# MIU60_REVB.net
KiCad netlist of a schematic drawn in EAGLE
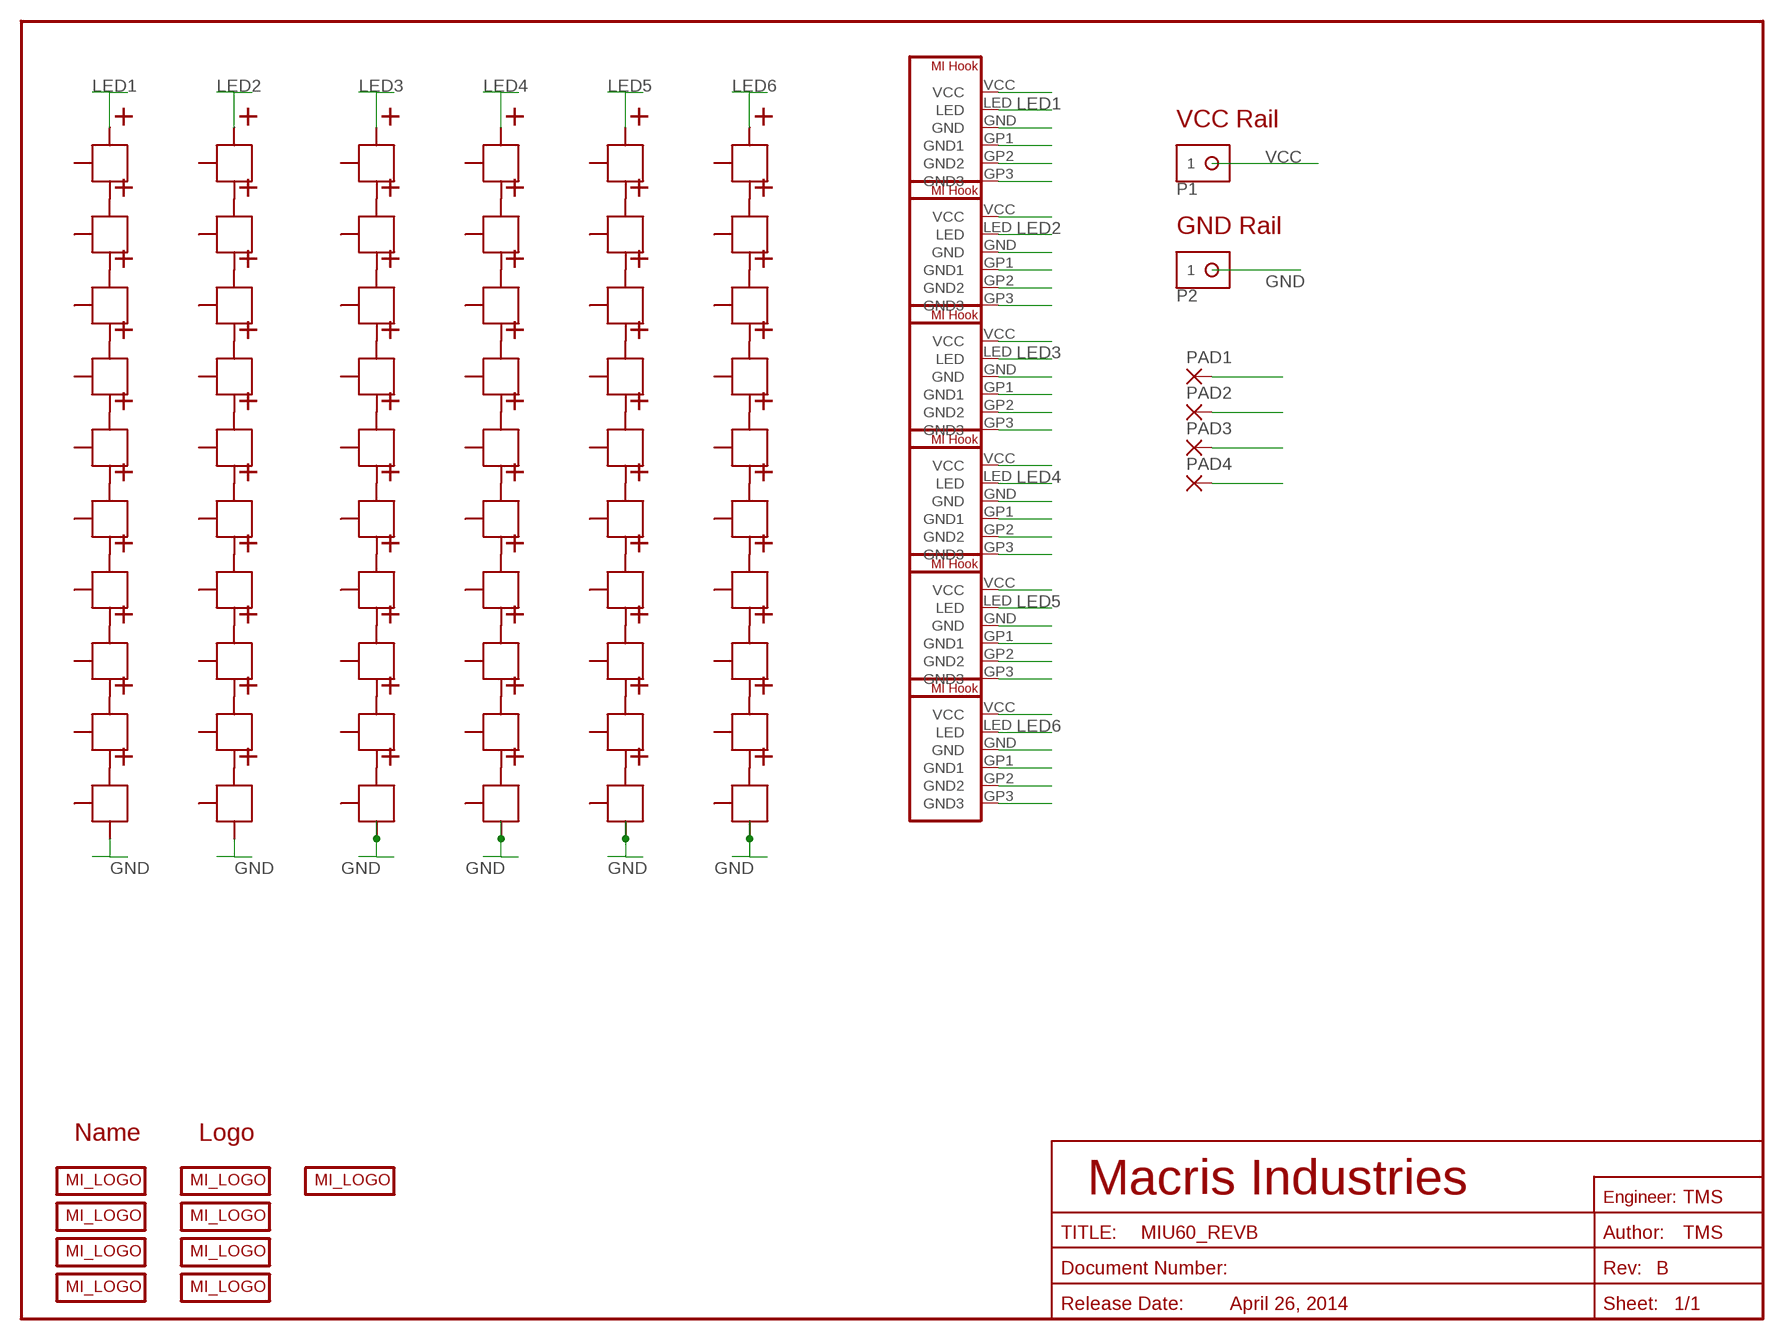
[diagram p0: schematic, sheet 1]

(export (version "E")
  (design (tool "Eeschema 10.0.6"))
  (components
    (comp (ref "P1")
      (value "PAD-10G")
      (footprint "eagle-import:PAD_10G")
      (libsource (lib "eagle-import") (part "PAD-10G"))
    )
    (comp (ref "P2")
      (value "PAD-10G")
      (footprint "eagle-import:PAD_10G")
      (libsource (lib "eagle-import") (part "PAD-10G"))
    )
    (comp (ref "PAD1")
      (value "SMD5")
      (footprint "eagle-import:SMD2,54-5,08")
      (libsource (lib "eagle-import") (part "SMD5"))
    )
    (comp (ref "PAD2")
      (value "SMD5")
      (footprint "eagle-import:SMD2,54-5,08")
      (libsource (lib "eagle-import") (part "SMD5"))
    )
    (comp (ref "PAD3")
      (value "SMD5")
      (footprint "eagle-import:SMD2,54-5,08")
      (libsource (lib "eagle-import") (part "SMD5"))
    )
    (comp (ref "PAD4")
      (value "SMD5")
      (footprint "eagle-import:SMD2,54-5,08")
      (libsource (lib "eagle-import") (part "SMD5"))
    )
    (comp (ref "U$1")
      (value "MI_LOGO-50MIL")
      (footprint "eagle-import:MI_LOGO_NAME_2")
      (libsource (lib "eagle-import") (part "MI_LOGO-NAME_TWO"))
    )
    (comp (ref "U$2")
      (value "MI_LOGO-2014_USA")
      (footprint "eagle-import:MACRIS_USA_LOGO")
      (libsource (lib "eagle-import") (part "MI_LOGO-2014_USA"))
    )
    (comp (ref "U$3")
      (value "MI_LOGO-50MIL")
      (footprint "eagle-import:MI_LOGO_NAME_2")
      (libsource (lib "eagle-import") (part "MI_LOGO-NAME_TWO"))
    )
    (comp (ref "U$4")
      (value "MI_LOGO-2014_USA")
      (footprint "eagle-import:MACRIS_USA_LOGO")
      (libsource (lib "eagle-import") (part "MI_LOGO-2014_USA"))
    )
    (comp (ref "U$5")
      (value "MI_LOGO-50MIL")
      (footprint "eagle-import:MI_LOGO_NAME_2")
      (libsource (lib "eagle-import") (part "MI_LOGO-NAME_TWO"))
    )
    (comp (ref "U$6")
      (value "MI_LOGO-50MIL")
      (footprint "eagle-import:MI_LOGO_NAME_2")
      (libsource (lib "eagle-import") (part "MI_LOGO-NAME_TWO"))
    )
    (comp (ref "U$7")
      (value "MI_LOGO-2014_USA")
      (footprint "eagle-import:MACRIS_USA_LOGO")
      (libsource (lib "eagle-import") (part "MI_LOGO-2014_USA"))
    )
    (comp (ref "U$8")
      (value "MI_LOGO-2014_USA")
      (footprint "eagle-import:MACRIS_USA_LOGO")
      (libsource (lib "eagle-import") (part "MI_LOGO-2014_USA"))
    )
    (comp (ref "U$9")
      (value "MI_DRIVER_HOOKUP")
      (footprint "eagle-import:MI_DRIVE_HOOKUP")
      (libsource (lib "eagle-import") (part "MI_DRIVER_HOOKUP"))
    )
    (comp (ref "U$10")
      (value "MI_DRIVER_HOOKUP")
      (footprint "eagle-import:MI_DRIVE_HOOKUP")
      (libsource (lib "eagle-import") (part "MI_DRIVER_HOOKUP"))
    )
    (comp (ref "U$11")
      (value "MI_DRIVER_HOOKUP")
      (footprint "eagle-import:MI_DRIVE_HOOKUP")
      (libsource (lib "eagle-import") (part "MI_DRIVER_HOOKUP"))
    )
    (comp (ref "U$12")
      (value "MI_DRIVER_HOOKUP")
      (footprint "eagle-import:MI_DRIVE_HOOKUP")
      (libsource (lib "eagle-import") (part "MI_DRIVER_HOOKUP"))
    )
    (comp (ref "U$13")
      (value "MI_DRIVER_HOOKUP")
      (footprint "eagle-import:MI_DRIVE_HOOKUP")
      (libsource (lib "eagle-import") (part "MI_DRIVER_HOOKUP"))
    )
    (comp (ref "U$14")
      (value "MI_DRIVER_HOOKUP")
      (footprint "eagle-import:MI_DRIVE_HOOKUP")
      (libsource (lib "eagle-import") (part "MI_DRIVER_HOOKUP"))
    )
    (comp (ref "U$15")
      (value "MI_LOGO")
      (footprint "eagle-import:MACRIS_MIU30")
      (libsource (lib "eagle-import") (part "MI_LOGO"))
    )
    (comp (ref "U$16")
      (value "CREE_XP")
      (footprint "eagle-import:XP")
      (libsource (lib "eagle-import") (part "CREE_XP"))
    )
    (comp (ref "U$17")
      (value "CREE_XP")
      (footprint "eagle-import:XP")
      (libsource (lib "eagle-import") (part "CREE_XP"))
    )
    (comp (ref "U$18")
      (value "CREE_XP")
      (footprint "eagle-import:XP")
      (libsource (lib "eagle-import") (part "CREE_XP"))
    )
    (comp (ref "U$19")
      (value "CREE_XP")
      (footprint "eagle-import:XP")
      (libsource (lib "eagle-import") (part "CREE_XP"))
    )
    (comp (ref "U$20")
      (value "CREE_XP")
      (footprint "eagle-import:XP")
      (libsource (lib "eagle-import") (part "CREE_XP"))
    )
    (comp (ref "U$21")
      (value "CREE_XP")
      (footprint "eagle-import:XP")
      (libsource (lib "eagle-import") (part "CREE_XP"))
    )
    (comp (ref "U$22")
      (value "CREE_XP")
      (footprint "eagle-import:XP")
      (libsource (lib "eagle-import") (part "CREE_XP"))
    )
    (comp (ref "U$23")
      (value "CREE_XP")
      (footprint "eagle-import:XP")
      (libsource (lib "eagle-import") (part "CREE_XP"))
    )
    (comp (ref "U$24")
      (value "CREE_XP")
      (footprint "eagle-import:XP")
      (libsource (lib "eagle-import") (part "CREE_XP"))
    )
    (comp (ref "U$25")
      (value "CREE_XP")
      (footprint "eagle-import:XP")
      (libsource (lib "eagle-import") (part "CREE_XP"))
    )
    (comp (ref "U$26")
      (value "CREE_XP")
      (footprint "eagle-import:XP")
      (libsource (lib "eagle-import") (part "CREE_XP"))
    )
    (comp (ref "U$27")
      (value "CREE_XP")
      (footprint "eagle-import:XP")
      (libsource (lib "eagle-import") (part "CREE_XP"))
    )
    (comp (ref "U$28")
      (value "CREE_XP")
      (footprint "eagle-import:XP")
      (libsource (lib "eagle-import") (part "CREE_XP"))
    )
    (comp (ref "U$29")
      (value "CREE_XP")
      (footprint "eagle-import:XP")
      (libsource (lib "eagle-import") (part "CREE_XP"))
    )
    (comp (ref "U$30")
      (value "CREE_XP")
      (footprint "eagle-import:XP")
      (libsource (lib "eagle-import") (part "CREE_XP"))
    )
    (comp (ref "U$31")
      (value "CREE_XP")
      (footprint "eagle-import:XP")
      (libsource (lib "eagle-import") (part "CREE_XP"))
    )
    (comp (ref "U$32")
      (value "CREE_XP")
      (footprint "eagle-import:XP")
      (libsource (lib "eagle-import") (part "CREE_XP"))
    )
    (comp (ref "U$33")
      (value "CREE_XP")
      (footprint "eagle-import:XP")
      (libsource (lib "eagle-import") (part "CREE_XP"))
    )
    (comp (ref "U$34")
      (value "CREE_XP")
      (footprint "eagle-import:XP")
      (libsource (lib "eagle-import") (part "CREE_XP"))
    )
    (comp (ref "U$35")
      (value "CREE_XP")
      (footprint "eagle-import:XP")
      (libsource (lib "eagle-import") (part "CREE_XP"))
    )
    (comp (ref "U$36")
      (value "CREE_XP")
      (footprint "eagle-import:XP")
      (libsource (lib "eagle-import") (part "CREE_XP"))
    )
    (comp (ref "U$37")
      (value "CREE_XP")
      (footprint "eagle-import:XP")
      (libsource (lib "eagle-import") (part "CREE_XP"))
    )
    (comp (ref "U$38")
      (value "CREE_XP")
      (footprint "eagle-import:XP")
      (libsource (lib "eagle-import") (part "CREE_XP"))
    )
    (comp (ref "U$39")
      (value "CREE_XP")
      (footprint "eagle-import:XP")
      (libsource (lib "eagle-import") (part "CREE_XP"))
    )
    (comp (ref "U$40")
      (value "CREE_XP")
      (footprint "eagle-import:XP")
      (libsource (lib "eagle-import") (part "CREE_XP"))
    )
    (comp (ref "U$41")
      (value "CREE_XP")
      (footprint "eagle-import:XP")
      (libsource (lib "eagle-import") (part "CREE_XP"))
    )
    (comp (ref "U$42")
      (value "CREE_XP")
      (footprint "eagle-import:XP")
      (libsource (lib "eagle-import") (part "CREE_XP"))
    )
    (comp (ref "U$43")
      (value "CREE_XP")
      (footprint "eagle-import:XP")
      (libsource (lib "eagle-import") (part "CREE_XP"))
    )
    (comp (ref "U$44")
      (value "CREE_XP")
      (footprint "eagle-import:XP")
      (libsource (lib "eagle-import") (part "CREE_XP"))
    )
    (comp (ref "U$45")
      (value "CREE_XP")
      (footprint "eagle-import:XP")
      (libsource (lib "eagle-import") (part "CREE_XP"))
    )
    (comp (ref "U$46")
      (value "CREE_XP")
      (footprint "eagle-import:XP")
      (libsource (lib "eagle-import") (part "CREE_XP"))
    )
    (comp (ref "U$47")
      (value "CREE_XP")
      (footprint "eagle-import:XP")
      (libsource (lib "eagle-import") (part "CREE_XP"))
    )
    (comp (ref "U$48")
      (value "CREE_XP")
      (footprint "eagle-import:XP")
      (libsource (lib "eagle-import") (part "CREE_XP"))
    )
    (comp (ref "U$49")
      (value "CREE_XP")
      (footprint "eagle-import:XP")
      (libsource (lib "eagle-import") (part "CREE_XP"))
    )
    (comp (ref "U$50")
      (value "CREE_XP")
      (footprint "eagle-import:XP")
      (libsource (lib "eagle-import") (part "CREE_XP"))
    )
    (comp (ref "U$51")
      (value "CREE_XP")
      (footprint "eagle-import:XP")
      (libsource (lib "eagle-import") (part "CREE_XP"))
    )
    (comp (ref "U$52")
      (value "CREE_XP")
      (footprint "eagle-import:XP")
      (libsource (lib "eagle-import") (part "CREE_XP"))
    )
    (comp (ref "U$53")
      (value "CREE_XP")
      (footprint "eagle-import:XP")
      (libsource (lib "eagle-import") (part "CREE_XP"))
    )
    (comp (ref "U$54")
      (value "CREE_XP")
      (footprint "eagle-import:XP")
      (libsource (lib "eagle-import") (part "CREE_XP"))
    )
    (comp (ref "U$55")
      (value "CREE_XP")
      (footprint "eagle-import:XP")
      (libsource (lib "eagle-import") (part "CREE_XP"))
    )
    (comp (ref "U$56")
      (value "CREE_XP")
      (footprint "eagle-import:XP")
      (libsource (lib "eagle-import") (part "CREE_XP"))
    )
    (comp (ref "U$57")
      (value "CREE_XP")
      (footprint "eagle-import:XP")
      (libsource (lib "eagle-import") (part "CREE_XP"))
    )
    (comp (ref "U$58")
      (value "CREE_XP")
      (footprint "eagle-import:XP")
      (libsource (lib "eagle-import") (part "CREE_XP"))
    )
    (comp (ref "U$59")
      (value "CREE_XP")
      (footprint "eagle-import:XP")
      (libsource (lib "eagle-import") (part "CREE_XP"))
    )
    (comp (ref "U$60")
      (value "CREE_XP")
      (footprint "eagle-import:XP")
      (libsource (lib "eagle-import") (part "CREE_XP"))
    )
    (comp (ref "U$61")
      (value "CREE_XP")
      (footprint "eagle-import:XP")
      (libsource (lib "eagle-import") (part "CREE_XP"))
    )
    (comp (ref "U$62")
      (value "CREE_XP")
      (footprint "eagle-import:XP")
      (libsource (lib "eagle-import") (part "CREE_XP"))
    )
    (comp (ref "U$63")
      (value "CREE_XP")
      (footprint "eagle-import:XP")
      (libsource (lib "eagle-import") (part "CREE_XP"))
    )
    (comp (ref "U$64")
      (value "CREE_XP")
      (footprint "eagle-import:XP")
      (libsource (lib "eagle-import") (part "CREE_XP"))
    )
    (comp (ref "U$65")
      (value "CREE_XP")
      (footprint "eagle-import:XP")
      (libsource (lib "eagle-import") (part "CREE_XP"))
    )
    (comp (ref "U$66")
      (value "CREE_XP")
      (footprint "eagle-import:XP")
      (libsource (lib "eagle-import") (part "CREE_XP"))
    )
    (comp (ref "U$67")
      (value "CREE_XP")
      (footprint "eagle-import:XP")
      (libsource (lib "eagle-import") (part "CREE_XP"))
    )
    (comp (ref "U$68")
      (value "CREE_XP")
      (footprint "eagle-import:XP")
      (libsource (lib "eagle-import") (part "CREE_XP"))
    )
    (comp (ref "U$69")
      (value "CREE_XP")
      (footprint "eagle-import:XP")
      (libsource (lib "eagle-import") (part "CREE_XP"))
    )
    (comp (ref "U$70")
      (value "CREE_XP")
      (footprint "eagle-import:XP")
      (libsource (lib "eagle-import") (part "CREE_XP"))
    )
    (comp (ref "U$71")
      (value "CREE_XP")
      (footprint "eagle-import:XP")
      (libsource (lib "eagle-import") (part "CREE_XP"))
    )
    (comp (ref "U$72")
      (value "CREE_XP")
      (footprint "eagle-import:XP")
      (libsource (lib "eagle-import") (part "CREE_XP"))
    )
    (comp (ref "U$73")
      (value "CREE_XP")
      (footprint "eagle-import:XP")
      (libsource (lib "eagle-import") (part "CREE_XP"))
    )
    (comp (ref "U$74")
      (value "CREE_XP")
      (footprint "eagle-import:XP")
      (libsource (lib "eagle-import") (part "CREE_XP"))
    )
    (comp (ref "U$75")
      (value "CREE_XP")
      (footprint "eagle-import:XP")
      (libsource (lib "eagle-import") (part "CREE_XP"))
    )
  )
  (nets
    (net (code "1") (name "/GND") (class "Default")
      (node (ref "P2") (pin "1") (pinfunction "1_1") (pintype "passive"))
      (node (ref "PAD3") (pin "1") (pinfunction "P_1") (pintype "passive"))
      (node (ref "PAD4") (pin "1") (pinfunction "P_1") (pintype "passive"))
      (node (ref "U$10") (pin "GND") (pinfunction "GND_GND") (pintype "bidirectional"))
      (node (ref "U$11") (pin "GND") (pinfunction "GND_GND") (pintype "bidirectional"))
      (node (ref "U$11") (pin "GP2") (pinfunction "GND2_GP2") (pintype "bidirectional"))
      (node (ref "U$12") (pin "GND") (pinfunction "GND_GND") (pintype "bidirectional"))
      (node (ref "U$12") (pin "GP2") (pinfunction "GND2_GP2") (pintype "bidirectional"))
      (node (ref "U$13") (pin "GND") (pinfunction "GND_GND") (pintype "bidirectional"))
      (node (ref "U$13") (pin "GP2") (pinfunction "GND2_GP2") (pintype "bidirectional"))
      (node (ref "U$14") (pin "GND") (pinfunction "GND_GND") (pintype "bidirectional"))
      (node (ref "U$14") (pin "GP2") (pinfunction "GND2_GP2") (pintype "bidirectional"))
      (node (ref "U$25") (pin "NEGATIVE") (pinfunction "NEGATIVE_NEGATIVE") (pintype "bidirectional"))
      (node (ref "U$25") (pin "NEGATIVE1") (pinfunction "NEGATIVE_NEGATIVE1") (pintype "bidirectional"))
      (node (ref "U$35") (pin "NEGATIVE") (pinfunction "NEGATIVE_NEGATIVE") (pintype "bidirectional"))
      (node (ref "U$35") (pin "NEGATIVE1") (pinfunction "NEGATIVE_NEGATIVE1") (pintype "bidirectional"))
      (node (ref "U$45") (pin "NEGATIVE") (pinfunction "NEGATIVE_NEGATIVE") (pintype "bidirectional"))
      (node (ref "U$45") (pin "NEGATIVE1") (pinfunction "NEGATIVE_NEGATIVE1") (pintype "bidirectional"))
      (node (ref "U$55") (pin "NEGATIVE") (pinfunction "NEGATIVE_NEGATIVE") (pintype "bidirectional"))
      (node (ref "U$55") (pin "NEGATIVE1") (pinfunction "NEGATIVE_NEGATIVE1") (pintype "bidirectional"))
      (node (ref "U$65") (pin "NEGATIVE") (pinfunction "NEGATIVE_NEGATIVE") (pintype "bidirectional"))
      (node (ref "U$65") (pin "NEGATIVE1") (pinfunction "NEGATIVE_NEGATIVE1") (pintype "bidirectional"))
      (node (ref "U$75") (pin "NEGATIVE") (pinfunction "NEGATIVE_NEGATIVE") (pintype "bidirectional"))
      (node (ref "U$75") (pin "NEGATIVE1") (pinfunction "NEGATIVE_NEGATIVE1") (pintype "bidirectional"))
      (node (ref "U$9") (pin "GND") (pinfunction "GND_GND") (pintype "bidirectional"))
      (node (ref "U$9") (pin "GP2") (pinfunction "GND2_GP2") (pintype "bidirectional"))
    )
    (net (code "2") (name "/LED1") (class "Default")
      (node (ref "U$16") (pin "POSITIVE") (pinfunction "POSITIVE_POSITIVE") (pintype "bidirectional"))
      (node (ref "U$16") (pin "POSITIVE1") (pinfunction "POSITIVE_POSITIVE1") (pintype "bidirectional"))
      (node (ref "U$9") (pin "LED") (pinfunction "LED_LED") (pintype "bidirectional"))
    )
    (net (code "3") (name "/LED2") (class "Default")
      (node (ref "U$10") (pin "LED") (pinfunction "LED_LED") (pintype "bidirectional"))
      (node (ref "U$26") (pin "POSITIVE") (pinfunction "POSITIVE_POSITIVE") (pintype "bidirectional"))
      (node (ref "U$26") (pin "POSITIVE1") (pinfunction "POSITIVE_POSITIVE1") (pintype "bidirectional"))
    )
    (net (code "4") (name "/LED3") (class "Default")
      (node (ref "U$11") (pin "LED") (pinfunction "LED_LED") (pintype "bidirectional"))
      (node (ref "U$36") (pin "POSITIVE") (pinfunction "POSITIVE_POSITIVE") (pintype "bidirectional"))
      (node (ref "U$36") (pin "POSITIVE1") (pinfunction "POSITIVE_POSITIVE1") (pintype "bidirectional"))
    )
    (net (code "5") (name "/LED4") (class "Default")
      (node (ref "U$12") (pin "LED") (pinfunction "LED_LED") (pintype "bidirectional"))
      (node (ref "U$46") (pin "POSITIVE") (pinfunction "POSITIVE_POSITIVE") (pintype "bidirectional"))
      (node (ref "U$46") (pin "POSITIVE1") (pinfunction "POSITIVE_POSITIVE1") (pintype "bidirectional"))
    )
    (net (code "6") (name "/LED5") (class "Default")
      (node (ref "U$13") (pin "LED") (pinfunction "LED_LED") (pintype "bidirectional"))
      (node (ref "U$56") (pin "POSITIVE") (pinfunction "POSITIVE_POSITIVE") (pintype "bidirectional"))
      (node (ref "U$56") (pin "POSITIVE1") (pinfunction "POSITIVE_POSITIVE1") (pintype "bidirectional"))
    )
    (net (code "7") (name "/LED6") (class "Default")
      (node (ref "U$14") (pin "LED") (pinfunction "LED_LED") (pintype "bidirectional"))
      (node (ref "U$66") (pin "POSITIVE") (pinfunction "POSITIVE_POSITIVE") (pintype "bidirectional"))
      (node (ref "U$66") (pin "POSITIVE1") (pinfunction "POSITIVE_POSITIVE1") (pintype "bidirectional"))
    )
    (net (code "8") (name "/VCC") (class "Default")
      (node (ref "P1") (pin "1") (pinfunction "1_1") (pintype "passive"))
      (node (ref "PAD1") (pin "1") (pinfunction "P_1") (pintype "passive"))
      (node (ref "PAD2") (pin "1") (pinfunction "P_1") (pintype "passive"))
      (node (ref "U$10") (pin "VCC") (pinfunction "VCC_VCC") (pintype "bidirectional"))
      (node (ref "U$11") (pin "VCC") (pinfunction "VCC_VCC") (pintype "bidirectional"))
      (node (ref "U$12") (pin "VCC") (pinfunction "VCC_VCC") (pintype "bidirectional"))
      (node (ref "U$13") (pin "VCC") (pinfunction "VCC_VCC") (pintype "bidirectional"))
      (node (ref "U$14") (pin "VCC") (pinfunction "VCC_VCC") (pintype "bidirectional"))
      (node (ref "U$9") (pin "VCC") (pinfunction "VCC_VCC") (pintype "bidirectional"))
    )
    (net (code "9") (name "Net-(U$16-NEGATIVE-PadNEGATIVE1)") (class "Default")
      (node (ref "U$16") (pin "NEGATIVE") (pinfunction "NEGATIVE_NEGATIVE") (pintype "bidirectional"))
      (node (ref "U$16") (pin "NEGATIVE1") (pinfunction "NEGATIVE_NEGATIVE1") (pintype "bidirectional"))
      (node (ref "U$17") (pin "POSITIVE") (pinfunction "POSITIVE_POSITIVE") (pintype "bidirectional"))
      (node (ref "U$17") (pin "POSITIVE1") (pinfunction "POSITIVE_POSITIVE1") (pintype "bidirectional"))
    )
    (net (code "10") (name "Net-(U$17-NEGATIVE-PadNEGATIVE1)") (class "Default")
      (node (ref "U$17") (pin "NEGATIVE") (pinfunction "NEGATIVE_NEGATIVE") (pintype "bidirectional"))
      (node (ref "U$17") (pin "NEGATIVE1") (pinfunction "NEGATIVE_NEGATIVE1") (pintype "bidirectional"))
      (node (ref "U$18") (pin "POSITIVE") (pinfunction "POSITIVE_POSITIVE") (pintype "bidirectional"))
      (node (ref "U$18") (pin "POSITIVE1") (pinfunction "POSITIVE_POSITIVE1") (pintype "bidirectional"))
    )
    (net (code "11") (name "Net-(U$18-NEGATIVE-PadNEGATIVE1)") (class "Default")
      (node (ref "U$18") (pin "NEGATIVE") (pinfunction "NEGATIVE_NEGATIVE") (pintype "bidirectional"))
      (node (ref "U$18") (pin "NEGATIVE1") (pinfunction "NEGATIVE_NEGATIVE1") (pintype "bidirectional"))
      (node (ref "U$19") (pin "POSITIVE") (pinfunction "POSITIVE_POSITIVE") (pintype "bidirectional"))
      (node (ref "U$19") (pin "POSITIVE1") (pinfunction "POSITIVE_POSITIVE1") (pintype "bidirectional"))
    )
    (net (code "12") (name "Net-(U$19-NEGATIVE-PadNEGATIVE1)") (class "Default")
      (node (ref "U$19") (pin "NEGATIVE") (pinfunction "NEGATIVE_NEGATIVE") (pintype "bidirectional"))
      (node (ref "U$19") (pin "NEGATIVE1") (pinfunction "NEGATIVE_NEGATIVE1") (pintype "bidirectional"))
      (node (ref "U$20") (pin "POSITIVE") (pinfunction "POSITIVE_POSITIVE") (pintype "bidirectional"))
      (node (ref "U$20") (pin "POSITIVE1") (pinfunction "POSITIVE_POSITIVE1") (pintype "bidirectional"))
    )
    (net (code "13") (name "Net-(U$20-NEGATIVE-PadNEGATIVE1)") (class "Default")
      (node (ref "U$20") (pin "NEGATIVE") (pinfunction "NEGATIVE_NEGATIVE") (pintype "bidirectional"))
      (node (ref "U$20") (pin "NEGATIVE1") (pinfunction "NEGATIVE_NEGATIVE1") (pintype "bidirectional"))
      (node (ref "U$21") (pin "POSITIVE") (pinfunction "POSITIVE_POSITIVE") (pintype "bidirectional"))
      (node (ref "U$21") (pin "POSITIVE1") (pinfunction "POSITIVE_POSITIVE1") (pintype "bidirectional"))
    )
    (net (code "14") (name "Net-(U$21-NEGATIVE-PadNEGATIVE1)") (class "Default")
      (node (ref "U$21") (pin "NEGATIVE") (pinfunction "NEGATIVE_NEGATIVE") (pintype "bidirectional"))
      (node (ref "U$21") (pin "NEGATIVE1") (pinfunction "NEGATIVE_NEGATIVE1") (pintype "bidirectional"))
      (node (ref "U$22") (pin "POSITIVE") (pinfunction "POSITIVE_POSITIVE") (pintype "bidirectional"))
      (node (ref "U$22") (pin "POSITIVE1") (pinfunction "POSITIVE_POSITIVE1") (pintype "bidirectional"))
    )
    (net (code "15") (name "Net-(U$22-NEGATIVE-PadNEGATIVE1)") (class "Default")
      (node (ref "U$22") (pin "NEGATIVE") (pinfunction "NEGATIVE_NEGATIVE") (pintype "bidirectional"))
      (node (ref "U$22") (pin "NEGATIVE1") (pinfunction "NEGATIVE_NEGATIVE1") (pintype "bidirectional"))
      (node (ref "U$23") (pin "POSITIVE") (pinfunction "POSITIVE_POSITIVE") (pintype "bidirectional"))
      (node (ref "U$23") (pin "POSITIVE1") (pinfunction "POSITIVE_POSITIVE1") (pintype "bidirectional"))
    )
    (net (code "16") (name "Net-(U$23-NEGATIVE-PadNEGATIVE1)") (class "Default")
      (node (ref "U$23") (pin "NEGATIVE") (pinfunction "NEGATIVE_NEGATIVE") (pintype "bidirectional"))
      (node (ref "U$23") (pin "NEGATIVE1") (pinfunction "NEGATIVE_NEGATIVE1") (pintype "bidirectional"))
      (node (ref "U$24") (pin "POSITIVE") (pinfunction "POSITIVE_POSITIVE") (pintype "bidirectional"))
      (node (ref "U$24") (pin "POSITIVE1") (pinfunction "POSITIVE_POSITIVE1") (pintype "bidirectional"))
    )
    (net (code "17") (name "Net-(U$24-NEGATIVE-PadNEGATIVE1)") (class "Default")
      (node (ref "U$24") (pin "NEGATIVE") (pinfunction "NEGATIVE_NEGATIVE") (pintype "bidirectional"))
      (node (ref "U$24") (pin "NEGATIVE1") (pinfunction "NEGATIVE_NEGATIVE1") (pintype "bidirectional"))
      (node (ref "U$25") (pin "POSITIVE") (pinfunction "POSITIVE_POSITIVE") (pintype "bidirectional"))
      (node (ref "U$25") (pin "POSITIVE1") (pinfunction "POSITIVE_POSITIVE1") (pintype "bidirectional"))
    )
    (net (code "18") (name "Net-(U$26-NEGATIVE-PadNEGATIVE1)") (class "Default")
      (node (ref "U$26") (pin "NEGATIVE") (pinfunction "NEGATIVE_NEGATIVE") (pintype "bidirectional"))
      (node (ref "U$26") (pin "NEGATIVE1") (pinfunction "NEGATIVE_NEGATIVE1") (pintype "bidirectional"))
      (node (ref "U$27") (pin "POSITIVE") (pinfunction "POSITIVE_POSITIVE") (pintype "bidirectional"))
      (node (ref "U$27") (pin "POSITIVE1") (pinfunction "POSITIVE_POSITIVE1") (pintype "bidirectional"))
    )
    (net (code "19") (name "Net-(U$27-NEGATIVE-PadNEGATIVE1)") (class "Default")
      (node (ref "U$27") (pin "NEGATIVE") (pinfunction "NEGATIVE_NEGATIVE") (pintype "bidirectional"))
      (node (ref "U$27") (pin "NEGATIVE1") (pinfunction "NEGATIVE_NEGATIVE1") (pintype "bidirectional"))
      (node (ref "U$28") (pin "POSITIVE") (pinfunction "POSITIVE_POSITIVE") (pintype "bidirectional"))
      (node (ref "U$28") (pin "POSITIVE1") (pinfunction "POSITIVE_POSITIVE1") (pintype "bidirectional"))
    )
    (net (code "20") (name "Net-(U$28-NEGATIVE-PadNEGATIVE1)") (class "Default")
      (node (ref "U$28") (pin "NEGATIVE") (pinfunction "NEGATIVE_NEGATIVE") (pintype "bidirectional"))
      (node (ref "U$28") (pin "NEGATIVE1") (pinfunction "NEGATIVE_NEGATIVE1") (pintype "bidirectional"))
      (node (ref "U$29") (pin "POSITIVE") (pinfunction "POSITIVE_POSITIVE") (pintype "bidirectional"))
      (node (ref "U$29") (pin "POSITIVE1") (pinfunction "POSITIVE_POSITIVE1") (pintype "bidirectional"))
    )
    (net (code "21") (name "Net-(U$29-NEGATIVE-PadNEGATIVE1)") (class "Default")
      (node (ref "U$29") (pin "NEGATIVE") (pinfunction "NEGATIVE_NEGATIVE") (pintype "bidirectional"))
      (node (ref "U$29") (pin "NEGATIVE1") (pinfunction "NEGATIVE_NEGATIVE1") (pintype "bidirectional"))
      (node (ref "U$30") (pin "POSITIVE") (pinfunction "POSITIVE_POSITIVE") (pintype "bidirectional"))
      (node (ref "U$30") (pin "POSITIVE1") (pinfunction "POSITIVE_POSITIVE1") (pintype "bidirectional"))
    )
    (net (code "22") (name "Net-(U$30-NEGATIVE-PadNEGATIVE1)") (class "Default")
      (node (ref "U$30") (pin "NEGATIVE") (pinfunction "NEGATIVE_NEGATIVE") (pintype "bidirectional"))
      (node (ref "U$30") (pin "NEGATIVE1") (pinfunction "NEGATIVE_NEGATIVE1") (pintype "bidirectional"))
      (node (ref "U$31") (pin "POSITIVE") (pinfunction "POSITIVE_POSITIVE") (pintype "bidirectional"))
      (node (ref "U$31") (pin "POSITIVE1") (pinfunction "POSITIVE_POSITIVE1") (pintype "bidirectional"))
    )
    (net (code "23") (name "Net-(U$31-NEGATIVE-PadNEGATIVE1)") (class "Default")
      (node (ref "U$31") (pin "NEGATIVE") (pinfunction "NEGATIVE_NEGATIVE") (pintype "bidirectional"))
      (node (ref "U$31") (pin "NEGATIVE1") (pinfunction "NEGATIVE_NEGATIVE1") (pintype "bidirectional"))
      (node (ref "U$32") (pin "POSITIVE") (pinfunction "POSITIVE_POSITIVE") (pintype "bidirectional"))
      (node (ref "U$32") (pin "POSITIVE1") (pinfunction "POSITIVE_POSITIVE1") (pintype "bidirectional"))
    )
    (net (code "24") (name "Net-(U$32-NEGATIVE-PadNEGATIVE1)") (class "Default")
      (node (ref "U$32") (pin "NEGATIVE") (pinfunction "NEGATIVE_NEGATIVE") (pintype "bidirectional"))
      (node (ref "U$32") (pin "NEGATIVE1") (pinfunction "NEGATIVE_NEGATIVE1") (pintype "bidirectional"))
      (node (ref "U$33") (pin "POSITIVE") (pinfunction "POSITIVE_POSITIVE") (pintype "bidirectional"))
      (node (ref "U$33") (pin "POSITIVE1") (pinfunction "POSITIVE_POSITIVE1") (pintype "bidirectional"))
    )
    (net (code "25") (name "Net-(U$33-NEGATIVE-PadNEGATIVE1)") (class "Default")
      (node (ref "U$33") (pin "NEGATIVE") (pinfunction "NEGATIVE_NEGATIVE") (pintype "bidirectional"))
      (node (ref "U$33") (pin "NEGATIVE1") (pinfunction "NEGATIVE_NEGATIVE1") (pintype "bidirectional"))
      (node (ref "U$34") (pin "POSITIVE") (pinfunction "POSITIVE_POSITIVE") (pintype "bidirectional"))
      (node (ref "U$34") (pin "POSITIVE1") (pinfunction "POSITIVE_POSITIVE1") (pintype "bidirectional"))
    )
    (net (code "26") (name "Net-(U$34-NEGATIVE-PadNEGATIVE1)") (class "Default")
      (node (ref "U$34") (pin "NEGATIVE") (pinfunction "NEGATIVE_NEGATIVE") (pintype "bidirectional"))
      (node (ref "U$34") (pin "NEGATIVE1") (pinfunction "NEGATIVE_NEGATIVE1") (pintype "bidirectional"))
      (node (ref "U$35") (pin "POSITIVE") (pinfunction "POSITIVE_POSITIVE") (pintype "bidirectional"))
      (node (ref "U$35") (pin "POSITIVE1") (pinfunction "POSITIVE_POSITIVE1") (pintype "bidirectional"))
    )
    (net (code "27") (name "Net-(U$36-NEGATIVE-PadNEGATIVE1)") (class "Default")
      (node (ref "U$36") (pin "NEGATIVE") (pinfunction "NEGATIVE_NEGATIVE") (pintype "bidirectional"))
      (node (ref "U$36") (pin "NEGATIVE1") (pinfunction "NEGATIVE_NEGATIVE1") (pintype "bidirectional"))
      (node (ref "U$37") (pin "POSITIVE") (pinfunction "POSITIVE_POSITIVE") (pintype "bidirectional"))
      (node (ref "U$37") (pin "POSITIVE1") (pinfunction "POSITIVE_POSITIVE1") (pintype "bidirectional"))
    )
    (net (code "28") (name "Net-(U$37-NEGATIVE-PadNEGATIVE1)") (class "Default")
      (node (ref "U$37") (pin "NEGATIVE") (pinfunction "NEGATIVE_NEGATIVE") (pintype "bidirectional"))
      (node (ref "U$37") (pin "NEGATIVE1") (pinfunction "NEGATIVE_NEGATIVE1") (pintype "bidirectional"))
      (node (ref "U$38") (pin "POSITIVE") (pinfunction "POSITIVE_POSITIVE") (pintype "bidirectional"))
      (node (ref "U$38") (pin "POSITIVE1") (pinfunction "POSITIVE_POSITIVE1") (pintype "bidirectional"))
    )
    (net (code "29") (name "Net-(U$38-NEGATIVE-PadNEGATIVE1)") (class "Default")
      (node (ref "U$38") (pin "NEGATIVE") (pinfunction "NEGATIVE_NEGATIVE") (pintype "bidirectional"))
      (node (ref "U$38") (pin "NEGATIVE1") (pinfunction "NEGATIVE_NEGATIVE1") (pintype "bidirectional"))
      (node (ref "U$39") (pin "POSITIVE") (pinfunction "POSITIVE_POSITIVE") (pintype "bidirectional"))
      (node (ref "U$39") (pin "POSITIVE1") (pinfunction "POSITIVE_POSITIVE1") (pintype "bidirectional"))
    )
    (net (code "30") (name "Net-(U$39-NEGATIVE-PadNEGATIVE1)") (class "Default")
      (node (ref "U$39") (pin "NEGATIVE") (pinfunction "NEGATIVE_NEGATIVE") (pintype "bidirectional"))
      (node (ref "U$39") (pin "NEGATIVE1") (pinfunction "NEGATIVE_NEGATIVE1") (pintype "bidirectional"))
      (node (ref "U$40") (pin "POSITIVE") (pinfunction "POSITIVE_POSITIVE") (pintype "bidirectional"))
      (node (ref "U$40") (pin "POSITIVE1") (pinfunction "POSITIVE_POSITIVE1") (pintype "bidirectional"))
    )
    (net (code "31") (name "Net-(U$40-NEGATIVE-PadNEGATIVE1)") (class "Default")
      (node (ref "U$40") (pin "NEGATIVE") (pinfunction "NEGATIVE_NEGATIVE") (pintype "bidirectional"))
      (node (ref "U$40") (pin "NEGATIVE1") (pinfunction "NEGATIVE_NEGATIVE1") (pintype "bidirectional"))
      (node (ref "U$41") (pin "POSITIVE") (pinfunction "POSITIVE_POSITIVE") (pintype "bidirectional"))
      (node (ref "U$41") (pin "POSITIVE1") (pinfunction "POSITIVE_POSITIVE1") (pintype "bidirectional"))
    )
    (net (code "32") (name "Net-(U$41-NEGATIVE-PadNEGATIVE1)") (class "Default")
      (node (ref "U$41") (pin "NEGATIVE") (pinfunction "NEGATIVE_NEGATIVE") (pintype "bidirectional"))
      (node (ref "U$41") (pin "NEGATIVE1") (pinfunction "NEGATIVE_NEGATIVE1") (pintype "bidirectional"))
      (node (ref "U$42") (pin "POSITIVE") (pinfunction "POSITIVE_POSITIVE") (pintype "bidirectional"))
      (node (ref "U$42") (pin "POSITIVE1") (pinfunction "POSITIVE_POSITIVE1") (pintype "bidirectional"))
    )
    (net (code "33") (name "Net-(U$42-NEGATIVE-PadNEGATIVE1)") (class "Default")
      (node (ref "U$42") (pin "NEGATIVE") (pinfunction "NEGATIVE_NEGATIVE") (pintype "bidirectional"))
      (node (ref "U$42") (pin "NEGATIVE1") (pinfunction "NEGATIVE_NEGATIVE1") (pintype "bidirectional"))
      (node (ref "U$43") (pin "POSITIVE") (pinfunction "POSITIVE_POSITIVE") (pintype "bidirectional"))
      (node (ref "U$43") (pin "POSITIVE1") (pinfunction "POSITIVE_POSITIVE1") (pintype "bidirectional"))
    )
    (net (code "34") (name "Net-(U$43-NEGATIVE-PadNEGATIVE1)") (class "Default")
      (node (ref "U$43") (pin "NEGATIVE") (pinfunction "NEGATIVE_NEGATIVE") (pintype "bidirectional"))
      (node (ref "U$43") (pin "NEGATIVE1") (pinfunction "NEGATIVE_NEGATIVE1") (pintype "bidirectional"))
      (node (ref "U$44") (pin "POSITIVE") (pinfunction "POSITIVE_POSITIVE") (pintype "bidirectional"))
      (node (ref "U$44") (pin "POSITIVE1") (pinfunction "POSITIVE_POSITIVE1") (pintype "bidirectional"))
    )
    (net (code "35") (name "Net-(U$44-NEGATIVE-PadNEGATIVE1)") (class "Default")
      (node (ref "U$44") (pin "NEGATIVE") (pinfunction "NEGATIVE_NEGATIVE") (pintype "bidirectional"))
      (node (ref "U$44") (pin "NEGATIVE1") (pinfunction "NEGATIVE_NEGATIVE1") (pintype "bidirectional"))
      (node (ref "U$45") (pin "POSITIVE") (pinfunction "POSITIVE_POSITIVE") (pintype "bidirectional"))
      (node (ref "U$45") (pin "POSITIVE1") (pinfunction "POSITIVE_POSITIVE1") (pintype "bidirectional"))
    )
    (net (code "36") (name "Net-(U$46-NEGATIVE-PadNEGATIVE1)") (class "Default")
      (node (ref "U$46") (pin "NEGATIVE") (pinfunction "NEGATIVE_NEGATIVE") (pintype "bidirectional"))
      (node (ref "U$46") (pin "NEGATIVE1") (pinfunction "NEGATIVE_NEGATIVE1") (pintype "bidirectional"))
      (node (ref "U$47") (pin "POSITIVE") (pinfunction "POSITIVE_POSITIVE") (pintype "bidirectional"))
      (node (ref "U$47") (pin "POSITIVE1") (pinfunction "POSITIVE_POSITIVE1") (pintype "bidirectional"))
    )
    (net (code "37") (name "Net-(U$47-NEGATIVE-PadNEGATIVE1)") (class "Default")
      (node (ref "U$47") (pin "NEGATIVE") (pinfunction "NEGATIVE_NEGATIVE") (pintype "bidirectional"))
      (node (ref "U$47") (pin "NEGATIVE1") (pinfunction "NEGATIVE_NEGATIVE1") (pintype "bidirectional"))
      (node (ref "U$48") (pin "POSITIVE") (pinfunction "POSITIVE_POSITIVE") (pintype "bidirectional"))
      (node (ref "U$48") (pin "POSITIVE1") (pinfunction "POSITIVE_POSITIVE1") (pintype "bidirectional"))
    )
    (net (code "38") (name "Net-(U$48-NEGATIVE-PadNEGATIVE1)") (class "Default")
      (node (ref "U$48") (pin "NEGATIVE") (pinfunction "NEGATIVE_NEGATIVE") (pintype "bidirectional"))
      (node (ref "U$48") (pin "NEGATIVE1") (pinfunction "NEGATIVE_NEGATIVE1") (pintype "bidirectional"))
      (node (ref "U$49") (pin "POSITIVE") (pinfunction "POSITIVE_POSITIVE") (pintype "bidirectional"))
      (node (ref "U$49") (pin "POSITIVE1") (pinfunction "POSITIVE_POSITIVE1") (pintype "bidirectional"))
    )
    (net (code "39") (name "Net-(U$49-NEGATIVE-PadNEGATIVE1)") (class "Default")
      (node (ref "U$49") (pin "NEGATIVE") (pinfunction "NEGATIVE_NEGATIVE") (pintype "bidirectional"))
      (node (ref "U$49") (pin "NEGATIVE1") (pinfunction "NEGATIVE_NEGATIVE1") (pintype "bidirectional"))
      (node (ref "U$50") (pin "POSITIVE") (pinfunction "POSITIVE_POSITIVE") (pintype "bidirectional"))
      (node (ref "U$50") (pin "POSITIVE1") (pinfunction "POSITIVE_POSITIVE1") (pintype "bidirectional"))
    )
    (net (code "40") (name "Net-(U$50-NEGATIVE-PadNEGATIVE1)") (class "Default")
      (node (ref "U$50") (pin "NEGATIVE") (pinfunction "NEGATIVE_NEGATIVE") (pintype "bidirectional"))
      (node (ref "U$50") (pin "NEGATIVE1") (pinfunction "NEGATIVE_NEGATIVE1") (pintype "bidirectional"))
      (node (ref "U$51") (pin "POSITIVE") (pinfunction "POSITIVE_POSITIVE") (pintype "bidirectional"))
      (node (ref "U$51") (pin "POSITIVE1") (pinfunction "POSITIVE_POSITIVE1") (pintype "bidirectional"))
    )
    (net (code "41") (name "Net-(U$51-NEGATIVE-PadNEGATIVE1)") (class "Default")
      (node (ref "U$51") (pin "NEGATIVE") (pinfunction "NEGATIVE_NEGATIVE") (pintype "bidirectional"))
      (node (ref "U$51") (pin "NEGATIVE1") (pinfunction "NEGATIVE_NEGATIVE1") (pintype "bidirectional"))
      (node (ref "U$52") (pin "POSITIVE") (pinfunction "POSITIVE_POSITIVE") (pintype "bidirectional"))
      (node (ref "U$52") (pin "POSITIVE1") (pinfunction "POSITIVE_POSITIVE1") (pintype "bidirectional"))
    )
    (net (code "42") (name "Net-(U$52-NEGATIVE-PadNEGATIVE1)") (class "Default")
      (node (ref "U$52") (pin "NEGATIVE") (pinfunction "NEGATIVE_NEGATIVE") (pintype "bidirectional"))
      (node (ref "U$52") (pin "NEGATIVE1") (pinfunction "NEGATIVE_NEGATIVE1") (pintype "bidirectional"))
      (node (ref "U$53") (pin "POSITIVE") (pinfunction "POSITIVE_POSITIVE") (pintype "bidirectional"))
      (node (ref "U$53") (pin "POSITIVE1") (pinfunction "POSITIVE_POSITIVE1") (pintype "bidirectional"))
    )
    (net (code "43") (name "Net-(U$53-NEGATIVE-PadNEGATIVE1)") (class "Default")
      (node (ref "U$53") (pin "NEGATIVE") (pinfunction "NEGATIVE_NEGATIVE") (pintype "bidirectional"))
      (node (ref "U$53") (pin "NEGATIVE1") (pinfunction "NEGATIVE_NEGATIVE1") (pintype "bidirectional"))
      (node (ref "U$54") (pin "POSITIVE") (pinfunction "POSITIVE_POSITIVE") (pintype "bidirectional"))
      (node (ref "U$54") (pin "POSITIVE1") (pinfunction "POSITIVE_POSITIVE1") (pintype "bidirectional"))
    )
    (net (code "44") (name "Net-(U$54-NEGATIVE-PadNEGATIVE1)") (class "Default")
      (node (ref "U$54") (pin "NEGATIVE") (pinfunction "NEGATIVE_NEGATIVE") (pintype "bidirectional"))
      (node (ref "U$54") (pin "NEGATIVE1") (pinfunction "NEGATIVE_NEGATIVE1") (pintype "bidirectional"))
      (node (ref "U$55") (pin "POSITIVE") (pinfunction "POSITIVE_POSITIVE") (pintype "bidirectional"))
      (node (ref "U$55") (pin "POSITIVE1") (pinfunction "POSITIVE_POSITIVE1") (pintype "bidirectional"))
    )
    (net (code "45") (name "Net-(U$56-NEGATIVE-PadNEGATIVE1)") (class "Default")
      (node (ref "U$56") (pin "NEGATIVE") (pinfunction "NEGATIVE_NEGATIVE") (pintype "bidirectional"))
      (node (ref "U$56") (pin "NEGATIVE1") (pinfunction "NEGATIVE_NEGATIVE1") (pintype "bidirectional"))
      (node (ref "U$57") (pin "POSITIVE") (pinfunction "POSITIVE_POSITIVE") (pintype "bidirectional"))
      (node (ref "U$57") (pin "POSITIVE1") (pinfunction "POSITIVE_POSITIVE1") (pintype "bidirectional"))
    )
    (net (code "46") (name "Net-(U$57-NEGATIVE-PadNEGATIVE1)") (class "Default")
      (node (ref "U$57") (pin "NEGATIVE") (pinfunction "NEGATIVE_NEGATIVE") (pintype "bidirectional"))
      (node (ref "U$57") (pin "NEGATIVE1") (pinfunction "NEGATIVE_NEGATIVE1") (pintype "bidirectional"))
      (node (ref "U$58") (pin "POSITIVE") (pinfunction "POSITIVE_POSITIVE") (pintype "bidirectional"))
      (node (ref "U$58") (pin "POSITIVE1") (pinfunction "POSITIVE_POSITIVE1") (pintype "bidirectional"))
    )
    (net (code "47") (name "Net-(U$58-NEGATIVE-PadNEGATIVE1)") (class "Default")
      (node (ref "U$58") (pin "NEGATIVE") (pinfunction "NEGATIVE_NEGATIVE") (pintype "bidirectional"))
      (node (ref "U$58") (pin "NEGATIVE1") (pinfunction "NEGATIVE_NEGATIVE1") (pintype "bidirectional"))
      (node (ref "U$59") (pin "POSITIVE") (pinfunction "POSITIVE_POSITIVE") (pintype "bidirectional"))
      (node (ref "U$59") (pin "POSITIVE1") (pinfunction "POSITIVE_POSITIVE1") (pintype "bidirectional"))
    )
    (net (code "48") (name "Net-(U$59-NEGATIVE-PadNEGATIVE1)") (class "Default")
      (node (ref "U$59") (pin "NEGATIVE") (pinfunction "NEGATIVE_NEGATIVE") (pintype "bidirectional"))
      (node (ref "U$59") (pin "NEGATIVE1") (pinfunction "NEGATIVE_NEGATIVE1") (pintype "bidirectional"))
      (node (ref "U$60") (pin "POSITIVE") (pinfunction "POSITIVE_POSITIVE") (pintype "bidirectional"))
      (node (ref "U$60") (pin "POSITIVE1") (pinfunction "POSITIVE_POSITIVE1") (pintype "bidirectional"))
    )
    (net (code "49") (name "Net-(U$60-NEGATIVE-PadNEGATIVE1)") (class "Default")
      (node (ref "U$60") (pin "NEGATIVE") (pinfunction "NEGATIVE_NEGATIVE") (pintype "bidirectional"))
      (node (ref "U$60") (pin "NEGATIVE1") (pinfunction "NEGATIVE_NEGATIVE1") (pintype "bidirectional"))
      (node (ref "U$61") (pin "POSITIVE") (pinfunction "POSITIVE_POSITIVE") (pintype "bidirectional"))
      (node (ref "U$61") (pin "POSITIVE1") (pinfunction "POSITIVE_POSITIVE1") (pintype "bidirectional"))
    )
    (net (code "50") (name "Net-(U$61-NEGATIVE-PadNEGATIVE1)") (class "Default")
      (node (ref "U$61") (pin "NEGATIVE") (pinfunction "NEGATIVE_NEGATIVE") (pintype "bidirectional"))
      (node (ref "U$61") (pin "NEGATIVE1") (pinfunction "NEGATIVE_NEGATIVE1") (pintype "bidirectional"))
      (node (ref "U$62") (pin "POSITIVE") (pinfunction "POSITIVE_POSITIVE") (pintype "bidirectional"))
      (node (ref "U$62") (pin "POSITIVE1") (pinfunction "POSITIVE_POSITIVE1") (pintype "bidirectional"))
    )
    (net (code "51") (name "Net-(U$62-NEGATIVE-PadNEGATIVE1)") (class "Default")
      (node (ref "U$62") (pin "NEGATIVE") (pinfunction "NEGATIVE_NEGATIVE") (pintype "bidirectional"))
      (node (ref "U$62") (pin "NEGATIVE1") (pinfunction "NEGATIVE_NEGATIVE1") (pintype "bidirectional"))
      (node (ref "U$63") (pin "POSITIVE") (pinfunction "POSITIVE_POSITIVE") (pintype "bidirectional"))
      (node (ref "U$63") (pin "POSITIVE1") (pinfunction "POSITIVE_POSITIVE1") (pintype "bidirectional"))
    )
    (net (code "52") (name "Net-(U$63-NEGATIVE-PadNEGATIVE1)") (class "Default")
      (node (ref "U$63") (pin "NEGATIVE") (pinfunction "NEGATIVE_NEGATIVE") (pintype "bidirectional"))
      (node (ref "U$63") (pin "NEGATIVE1") (pinfunction "NEGATIVE_NEGATIVE1") (pintype "bidirectional"))
      (node (ref "U$64") (pin "POSITIVE") (pinfunction "POSITIVE_POSITIVE") (pintype "bidirectional"))
      (node (ref "U$64") (pin "POSITIVE1") (pinfunction "POSITIVE_POSITIVE1") (pintype "bidirectional"))
    )
    (net (code "53") (name "Net-(U$64-NEGATIVE-PadNEGATIVE1)") (class "Default")
      (node (ref "U$64") (pin "NEGATIVE") (pinfunction "NEGATIVE_NEGATIVE") (pintype "bidirectional"))
      (node (ref "U$64") (pin "NEGATIVE1") (pinfunction "NEGATIVE_NEGATIVE1") (pintype "bidirectional"))
      (node (ref "U$65") (pin "POSITIVE") (pinfunction "POSITIVE_POSITIVE") (pintype "bidirectional"))
      (node (ref "U$65") (pin "POSITIVE1") (pinfunction "POSITIVE_POSITIVE1") (pintype "bidirectional"))
    )
    (net (code "54") (name "Net-(U$66-NEGATIVE-PadNEGATIVE1)") (class "Default")
      (node (ref "U$66") (pin "NEGATIVE") (pinfunction "NEGATIVE_NEGATIVE") (pintype "bidirectional"))
      (node (ref "U$66") (pin "NEGATIVE1") (pinfunction "NEGATIVE_NEGATIVE1") (pintype "bidirectional"))
      (node (ref "U$67") (pin "POSITIVE") (pinfunction "POSITIVE_POSITIVE") (pintype "bidirectional"))
      (node (ref "U$67") (pin "POSITIVE1") (pinfunction "POSITIVE_POSITIVE1") (pintype "bidirectional"))
    )
    (net (code "55") (name "Net-(U$67-NEGATIVE-PadNEGATIVE1)") (class "Default")
      (node (ref "U$67") (pin "NEGATIVE") (pinfunction "NEGATIVE_NEGATIVE") (pintype "bidirectional"))
      (node (ref "U$67") (pin "NEGATIVE1") (pinfunction "NEGATIVE_NEGATIVE1") (pintype "bidirectional"))
      (node (ref "U$68") (pin "POSITIVE") (pinfunction "POSITIVE_POSITIVE") (pintype "bidirectional"))
      (node (ref "U$68") (pin "POSITIVE1") (pinfunction "POSITIVE_POSITIVE1") (pintype "bidirectional"))
    )
    (net (code "56") (name "Net-(U$68-NEGATIVE-PadNEGATIVE1)") (class "Default")
      (node (ref "U$68") (pin "NEGATIVE") (pinfunction "NEGATIVE_NEGATIVE") (pintype "bidirectional"))
      (node (ref "U$68") (pin "NEGATIVE1") (pinfunction "NEGATIVE_NEGATIVE1") (pintype "bidirectional"))
      (node (ref "U$69") (pin "POSITIVE") (pinfunction "POSITIVE_POSITIVE") (pintype "bidirectional"))
      (node (ref "U$69") (pin "POSITIVE1") (pinfunction "POSITIVE_POSITIVE1") (pintype "bidirectional"))
    )
    (net (code "57") (name "Net-(U$69-NEGATIVE-PadNEGATIVE1)") (class "Default")
      (node (ref "U$69") (pin "NEGATIVE") (pinfunction "NEGATIVE_NEGATIVE") (pintype "bidirectional"))
      (node (ref "U$69") (pin "NEGATIVE1") (pinfunction "NEGATIVE_NEGATIVE1") (pintype "bidirectional"))
      (node (ref "U$70") (pin "POSITIVE") (pinfunction "POSITIVE_POSITIVE") (pintype "bidirectional"))
      (node (ref "U$70") (pin "POSITIVE1") (pinfunction "POSITIVE_POSITIVE1") (pintype "bidirectional"))
    )
    (net (code "58") (name "Net-(U$70-NEGATIVE-PadNEGATIVE1)") (class "Default")
      (node (ref "U$70") (pin "NEGATIVE") (pinfunction "NEGATIVE_NEGATIVE") (pintype "bidirectional"))
      (node (ref "U$70") (pin "NEGATIVE1") (pinfunction "NEGATIVE_NEGATIVE1") (pintype "bidirectional"))
      (node (ref "U$71") (pin "POSITIVE") (pinfunction "POSITIVE_POSITIVE") (pintype "bidirectional"))
      (node (ref "U$71") (pin "POSITIVE1") (pinfunction "POSITIVE_POSITIVE1") (pintype "bidirectional"))
    )
    (net (code "59") (name "Net-(U$71-NEGATIVE-PadNEGATIVE1)") (class "Default")
      (node (ref "U$71") (pin "NEGATIVE") (pinfunction "NEGATIVE_NEGATIVE") (pintype "bidirectional"))
      (node (ref "U$71") (pin "NEGATIVE1") (pinfunction "NEGATIVE_NEGATIVE1") (pintype "bidirectional"))
      (node (ref "U$72") (pin "POSITIVE") (pinfunction "POSITIVE_POSITIVE") (pintype "bidirectional"))
      (node (ref "U$72") (pin "POSITIVE1") (pinfunction "POSITIVE_POSITIVE1") (pintype "bidirectional"))
    )
    (net (code "60") (name "Net-(U$72-NEGATIVE-PadNEGATIVE1)") (class "Default")
      (node (ref "U$72") (pin "NEGATIVE") (pinfunction "NEGATIVE_NEGATIVE") (pintype "bidirectional"))
      (node (ref "U$72") (pin "NEGATIVE1") (pinfunction "NEGATIVE_NEGATIVE1") (pintype "bidirectional"))
      (node (ref "U$73") (pin "POSITIVE") (pinfunction "POSITIVE_POSITIVE") (pintype "bidirectional"))
      (node (ref "U$73") (pin "POSITIVE1") (pinfunction "POSITIVE_POSITIVE1") (pintype "bidirectional"))
    )
    (net (code "61") (name "Net-(U$73-NEGATIVE-PadNEGATIVE1)") (class "Default")
      (node (ref "U$73") (pin "NEGATIVE") (pinfunction "NEGATIVE_NEGATIVE") (pintype "bidirectional"))
      (node (ref "U$73") (pin "NEGATIVE1") (pinfunction "NEGATIVE_NEGATIVE1") (pintype "bidirectional"))
      (node (ref "U$74") (pin "POSITIVE") (pinfunction "POSITIVE_POSITIVE") (pintype "bidirectional"))
      (node (ref "U$74") (pin "POSITIVE1") (pinfunction "POSITIVE_POSITIVE1") (pintype "bidirectional"))
    )
    (net (code "62") (name "Net-(U$74-NEGATIVE-PadNEGATIVE1)") (class "Default")
      (node (ref "U$74") (pin "NEGATIVE") (pinfunction "NEGATIVE_NEGATIVE") (pintype "bidirectional"))
      (node (ref "U$74") (pin "NEGATIVE1") (pinfunction "NEGATIVE_NEGATIVE1") (pintype "bidirectional"))
      (node (ref "U$75") (pin "POSITIVE") (pinfunction "POSITIVE_POSITIVE") (pintype "bidirectional"))
      (node (ref "U$75") (pin "POSITIVE1") (pinfunction "POSITIVE_POSITIVE1") (pintype "bidirectional"))
    )
    (net (code "63") (name "unconnected-(U$9-GND1-PadGP1)") (class "Default")
      (node (ref "U$9") (pin "GP1") (pinfunction "GND1_GP1") (pintype "bidirectional"))
    )
    (net (code "64") (name "unconnected-(U$9-GND3-PadGP3)") (class "Default")
      (node (ref "U$9") (pin "GP3") (pinfunction "GND3_GP3") (pintype "bidirectional"))
    )
    (net (code "65") (name "unconnected-(U$10-GND1-PadGP1)") (class "Default")
      (node (ref "U$10") (pin "GP1") (pinfunction "GND1_GP1") (pintype "bidirectional"))
    )
    (net (code "66") (name "unconnected-(U$10-GND2-PadGP2)") (class "Default")
      (node (ref "U$10") (pin "GP2") (pinfunction "GND2_GP2") (pintype "bidirectional"))
    )
    (net (code "67") (name "unconnected-(U$10-GND3-PadGP3)") (class "Default")
      (node (ref "U$10") (pin "GP3") (pinfunction "GND3_GP3") (pintype "bidirectional"))
    )
    (net (code "68") (name "unconnected-(U$11-GND1-PadGP1)") (class "Default")
      (node (ref "U$11") (pin "GP1") (pinfunction "GND1_GP1") (pintype "bidirectional"))
    )
    (net (code "69") (name "unconnected-(U$11-GND3-PadGP3)") (class "Default")
      (node (ref "U$11") (pin "GP3") (pinfunction "GND3_GP3") (pintype "bidirectional"))
    )
    (net (code "70") (name "unconnected-(U$12-GND1-PadGP1)") (class "Default")
      (node (ref "U$12") (pin "GP1") (pinfunction "GND1_GP1") (pintype "bidirectional"))
    )
    (net (code "71") (name "unconnected-(U$12-GND3-PadGP3)") (class "Default")
      (node (ref "U$12") (pin "GP3") (pinfunction "GND3_GP3") (pintype "bidirectional"))
    )
    (net (code "72") (name "unconnected-(U$13-GND1-PadGP1)") (class "Default")
      (node (ref "U$13") (pin "GP1") (pinfunction "GND1_GP1") (pintype "bidirectional"))
    )
    (net (code "73") (name "unconnected-(U$13-GND3-PadGP3)") (class "Default")
      (node (ref "U$13") (pin "GP3") (pinfunction "GND3_GP3") (pintype "bidirectional"))
    )
    (net (code "74") (name "unconnected-(U$14-GND1-PadGP1)") (class "Default")
      (node (ref "U$14") (pin "GP1") (pinfunction "GND1_GP1") (pintype "bidirectional"))
    )
    (net (code "75") (name "unconnected-(U$14-GND3-PadGP3)") (class "Default")
      (node (ref "U$14") (pin "GP3") (pinfunction "GND3_GP3") (pintype "bidirectional"))
    )
    (net (code "76") (name "unconnected-(U$16-PadTHERMAL)") (class "Default")
      (node (ref "U$16") (pin "THERMAL") (pinfunction "THERMAL_THERMAL") (pintype "bidirectional"))
    )
    (net (code "77") (name "unconnected-(U$17-PadTHERMAL)") (class "Default")
      (node (ref "U$17") (pin "THERMAL") (pinfunction "THERMAL_THERMAL") (pintype "bidirectional"))
    )
    (net (code "78") (name "unconnected-(U$18-PadTHERMAL)") (class "Default")
      (node (ref "U$18") (pin "THERMAL") (pinfunction "THERMAL_THERMAL") (pintype "bidirectional"))
    )
    (net (code "79") (name "unconnected-(U$19-PadTHERMAL)") (class "Default")
      (node (ref "U$19") (pin "THERMAL") (pinfunction "THERMAL_THERMAL") (pintype "bidirectional"))
    )
    (net (code "80") (name "unconnected-(U$20-PadTHERMAL)") (class "Default")
      (node (ref "U$20") (pin "THERMAL") (pinfunction "THERMAL_THERMAL") (pintype "bidirectional"))
    )
    (net (code "81") (name "unconnected-(U$21-PadTHERMAL)") (class "Default")
      (node (ref "U$21") (pin "THERMAL") (pinfunction "THERMAL_THERMAL") (pintype "bidirectional"))
    )
    (net (code "82") (name "unconnected-(U$22-PadTHERMAL)") (class "Default")
      (node (ref "U$22") (pin "THERMAL") (pinfunction "THERMAL_THERMAL") (pintype "bidirectional"))
    )
    (net (code "83") (name "unconnected-(U$23-PadTHERMAL)") (class "Default")
      (node (ref "U$23") (pin "THERMAL") (pinfunction "THERMAL_THERMAL") (pintype "bidirectional"))
    )
    (net (code "84") (name "unconnected-(U$24-PadTHERMAL)") (class "Default")
      (node (ref "U$24") (pin "THERMAL") (pinfunction "THERMAL_THERMAL") (pintype "bidirectional"))
    )
    (net (code "85") (name "unconnected-(U$25-PadTHERMAL)") (class "Default")
      (node (ref "U$25") (pin "THERMAL") (pinfunction "THERMAL_THERMAL") (pintype "bidirectional"))
    )
    (net (code "86") (name "unconnected-(U$26-PadTHERMAL)") (class "Default")
      (node (ref "U$26") (pin "THERMAL") (pinfunction "THERMAL_THERMAL") (pintype "bidirectional"))
    )
    (net (code "87") (name "unconnected-(U$27-PadTHERMAL)") (class "Default")
      (node (ref "U$27") (pin "THERMAL") (pinfunction "THERMAL_THERMAL") (pintype "bidirectional"))
    )
    (net (code "88") (name "unconnected-(U$28-PadTHERMAL)") (class "Default")
      (node (ref "U$28") (pin "THERMAL") (pinfunction "THERMAL_THERMAL") (pintype "bidirectional"))
    )
    (net (code "89") (name "unconnected-(U$29-PadTHERMAL)") (class "Default")
      (node (ref "U$29") (pin "THERMAL") (pinfunction "THERMAL_THERMAL") (pintype "bidirectional"))
    )
    (net (code "90") (name "unconnected-(U$30-PadTHERMAL)") (class "Default")
      (node (ref "U$30") (pin "THERMAL") (pinfunction "THERMAL_THERMAL") (pintype "bidirectional"))
    )
    (net (code "91") (name "unconnected-(U$31-PadTHERMAL)") (class "Default")
      (node (ref "U$31") (pin "THERMAL") (pinfunction "THERMAL_THERMAL") (pintype "bidirectional"))
    )
    (net (code "92") (name "unconnected-(U$32-PadTHERMAL)") (class "Default")
      (node (ref "U$32") (pin "THERMAL") (pinfunction "THERMAL_THERMAL") (pintype "bidirectional"))
    )
    (net (code "93") (name "unconnected-(U$33-PadTHERMAL)") (class "Default")
      (node (ref "U$33") (pin "THERMAL") (pinfunction "THERMAL_THERMAL") (pintype "bidirectional"))
    )
    (net (code "94") (name "unconnected-(U$34-PadTHERMAL)") (class "Default")
      (node (ref "U$34") (pin "THERMAL") (pinfunction "THERMAL_THERMAL") (pintype "bidirectional"))
    )
    (net (code "95") (name "unconnected-(U$35-PadTHERMAL)") (class "Default")
      (node (ref "U$35") (pin "THERMAL") (pinfunction "THERMAL_THERMAL") (pintype "bidirectional"))
    )
    (net (code "96") (name "unconnected-(U$36-PadTHERMAL)") (class "Default")
      (node (ref "U$36") (pin "THERMAL") (pinfunction "THERMAL_THERMAL") (pintype "bidirectional"))
    )
    (net (code "97") (name "unconnected-(U$37-PadTHERMAL)") (class "Default")
      (node (ref "U$37") (pin "THERMAL") (pinfunction "THERMAL_THERMAL") (pintype "bidirectional"))
    )
    (net (code "98") (name "unconnected-(U$38-PadTHERMAL)") (class "Default")
      (node (ref "U$38") (pin "THERMAL") (pinfunction "THERMAL_THERMAL") (pintype "bidirectional"))
    )
    (net (code "99") (name "unconnected-(U$39-PadTHERMAL)") (class "Default")
      (node (ref "U$39") (pin "THERMAL") (pinfunction "THERMAL_THERMAL") (pintype "bidirectional"))
    )
    (net (code "100") (name "unconnected-(U$40-PadTHERMAL)") (class "Default")
      (node (ref "U$40") (pin "THERMAL") (pinfunction "THERMAL_THERMAL") (pintype "bidirectional"))
    )
    (net (code "101") (name "unconnected-(U$41-PadTHERMAL)") (class "Default")
      (node (ref "U$41") (pin "THERMAL") (pinfunction "THERMAL_THERMAL") (pintype "bidirectional"))
    )
    (net (code "102") (name "unconnected-(U$42-PadTHERMAL)") (class "Default")
      (node (ref "U$42") (pin "THERMAL") (pinfunction "THERMAL_THERMAL") (pintype "bidirectional"))
    )
    (net (code "103") (name "unconnected-(U$43-PadTHERMAL)") (class "Default")
      (node (ref "U$43") (pin "THERMAL") (pinfunction "THERMAL_THERMAL") (pintype "bidirectional"))
    )
    (net (code "104") (name "unconnected-(U$44-PadTHERMAL)") (class "Default")
      (node (ref "U$44") (pin "THERMAL") (pinfunction "THERMAL_THERMAL") (pintype "bidirectional"))
    )
    (net (code "105") (name "unconnected-(U$45-PadTHERMAL)") (class "Default")
      (node (ref "U$45") (pin "THERMAL") (pinfunction "THERMAL_THERMAL") (pintype "bidirectional"))
    )
    (net (code "106") (name "unconnected-(U$46-PadTHERMAL)") (class "Default")
      (node (ref "U$46") (pin "THERMAL") (pinfunction "THERMAL_THERMAL") (pintype "bidirectional"))
    )
    (net (code "107") (name "unconnected-(U$47-PadTHERMAL)") (class "Default")
      (node (ref "U$47") (pin "THERMAL") (pinfunction "THERMAL_THERMAL") (pintype "bidirectional"))
    )
    (net (code "108") (name "unconnected-(U$48-PadTHERMAL)") (class "Default")
      (node (ref "U$48") (pin "THERMAL") (pinfunction "THERMAL_THERMAL") (pintype "bidirectional"))
    )
    (net (code "109") (name "unconnected-(U$49-PadTHERMAL)") (class "Default")
      (node (ref "U$49") (pin "THERMAL") (pinfunction "THERMAL_THERMAL") (pintype "bidirectional"))
    )
    (net (code "110") (name "unconnected-(U$50-PadTHERMAL)") (class "Default")
      (node (ref "U$50") (pin "THERMAL") (pinfunction "THERMAL_THERMAL") (pintype "bidirectional"))
    )
    (net (code "111") (name "unconnected-(U$51-PadTHERMAL)") (class "Default")
      (node (ref "U$51") (pin "THERMAL") (pinfunction "THERMAL_THERMAL") (pintype "bidirectional"))
    )
    (net (code "112") (name "unconnected-(U$52-PadTHERMAL)") (class "Default")
      (node (ref "U$52") (pin "THERMAL") (pinfunction "THERMAL_THERMAL") (pintype "bidirectional"))
    )
    (net (code "113") (name "unconnected-(U$53-PadTHERMAL)") (class "Default")
      (node (ref "U$53") (pin "THERMAL") (pinfunction "THERMAL_THERMAL") (pintype "bidirectional"))
    )
    (net (code "114") (name "unconnected-(U$54-PadTHERMAL)") (class "Default")
      (node (ref "U$54") (pin "THERMAL") (pinfunction "THERMAL_THERMAL") (pintype "bidirectional"))
    )
    (net (code "115") (name "unconnected-(U$55-PadTHERMAL)") (class "Default")
      (node (ref "U$55") (pin "THERMAL") (pinfunction "THERMAL_THERMAL") (pintype "bidirectional"))
    )
    (net (code "116") (name "unconnected-(U$56-PadTHERMAL)") (class "Default")
      (node (ref "U$56") (pin "THERMAL") (pinfunction "THERMAL_THERMAL") (pintype "bidirectional"))
    )
    (net (code "117") (name "unconnected-(U$57-PadTHERMAL)") (class "Default")
      (node (ref "U$57") (pin "THERMAL") (pinfunction "THERMAL_THERMAL") (pintype "bidirectional"))
    )
    (net (code "118") (name "unconnected-(U$58-PadTHERMAL)") (class "Default")
      (node (ref "U$58") (pin "THERMAL") (pinfunction "THERMAL_THERMAL") (pintype "bidirectional"))
    )
    (net (code "119") (name "unconnected-(U$59-PadTHERMAL)") (class "Default")
      (node (ref "U$59") (pin "THERMAL") (pinfunction "THERMAL_THERMAL") (pintype "bidirectional"))
    )
    (net (code "120") (name "unconnected-(U$60-PadTHERMAL)") (class "Default")
      (node (ref "U$60") (pin "THERMAL") (pinfunction "THERMAL_THERMAL") (pintype "bidirectional"))
    )
    (net (code "121") (name "unconnected-(U$61-PadTHERMAL)") (class "Default")
      (node (ref "U$61") (pin "THERMAL") (pinfunction "THERMAL_THERMAL") (pintype "bidirectional"))
    )
    (net (code "122") (name "unconnected-(U$62-PadTHERMAL)") (class "Default")
      (node (ref "U$62") (pin "THERMAL") (pinfunction "THERMAL_THERMAL") (pintype "bidirectional"))
    )
    (net (code "123") (name "unconnected-(U$63-PadTHERMAL)") (class "Default")
      (node (ref "U$63") (pin "THERMAL") (pinfunction "THERMAL_THERMAL") (pintype "bidirectional"))
    )
    (net (code "124") (name "unconnected-(U$64-PadTHERMAL)") (class "Default")
      (node (ref "U$64") (pin "THERMAL") (pinfunction "THERMAL_THERMAL") (pintype "bidirectional"))
    )
    (net (code "125") (name "unconnected-(U$65-PadTHERMAL)") (class "Default")
      (node (ref "U$65") (pin "THERMAL") (pinfunction "THERMAL_THERMAL") (pintype "bidirectional"))
    )
    (net (code "126") (name "unconnected-(U$66-PadTHERMAL)") (class "Default")
      (node (ref "U$66") (pin "THERMAL") (pinfunction "THERMAL_THERMAL") (pintype "bidirectional"))
    )
    (net (code "127") (name "unconnected-(U$67-PadTHERMAL)") (class "Default")
      (node (ref "U$67") (pin "THERMAL") (pinfunction "THERMAL_THERMAL") (pintype "bidirectional"))
    )
    (net (code "128") (name "unconnected-(U$68-PadTHERMAL)") (class "Default")
      (node (ref "U$68") (pin "THERMAL") (pinfunction "THERMAL_THERMAL") (pintype "bidirectional"))
    )
    (net (code "129") (name "unconnected-(U$69-PadTHERMAL)") (class "Default")
      (node (ref "U$69") (pin "THERMAL") (pinfunction "THERMAL_THERMAL") (pintype "bidirectional"))
    )
    (net (code "130") (name "unconnected-(U$70-PadTHERMAL)") (class "Default")
      (node (ref "U$70") (pin "THERMAL") (pinfunction "THERMAL_THERMAL") (pintype "bidirectional"))
    )
    (net (code "131") (name "unconnected-(U$71-PadTHERMAL)") (class "Default")
      (node (ref "U$71") (pin "THERMAL") (pinfunction "THERMAL_THERMAL") (pintype "bidirectional"))
    )
    (net (code "132") (name "unconnected-(U$72-PadTHERMAL)") (class "Default")
      (node (ref "U$72") (pin "THERMAL") (pinfunction "THERMAL_THERMAL") (pintype "bidirectional"))
    )
    (net (code "133") (name "unconnected-(U$73-PadTHERMAL)") (class "Default")
      (node (ref "U$73") (pin "THERMAL") (pinfunction "THERMAL_THERMAL") (pintype "bidirectional"))
    )
    (net (code "134") (name "unconnected-(U$74-PadTHERMAL)") (class "Default")
      (node (ref "U$74") (pin "THERMAL") (pinfunction "THERMAL_THERMAL") (pintype "bidirectional"))
    )
    (net (code "135") (name "unconnected-(U$75-PadTHERMAL)") (class "Default")
      (node (ref "U$75") (pin "THERMAL") (pinfunction "THERMAL_THERMAL") (pintype "bidirectional"))
    )
  )
)
